# MCU_BLE_Module.net
KiCad netlist of a schematic drawn in Altium Designer
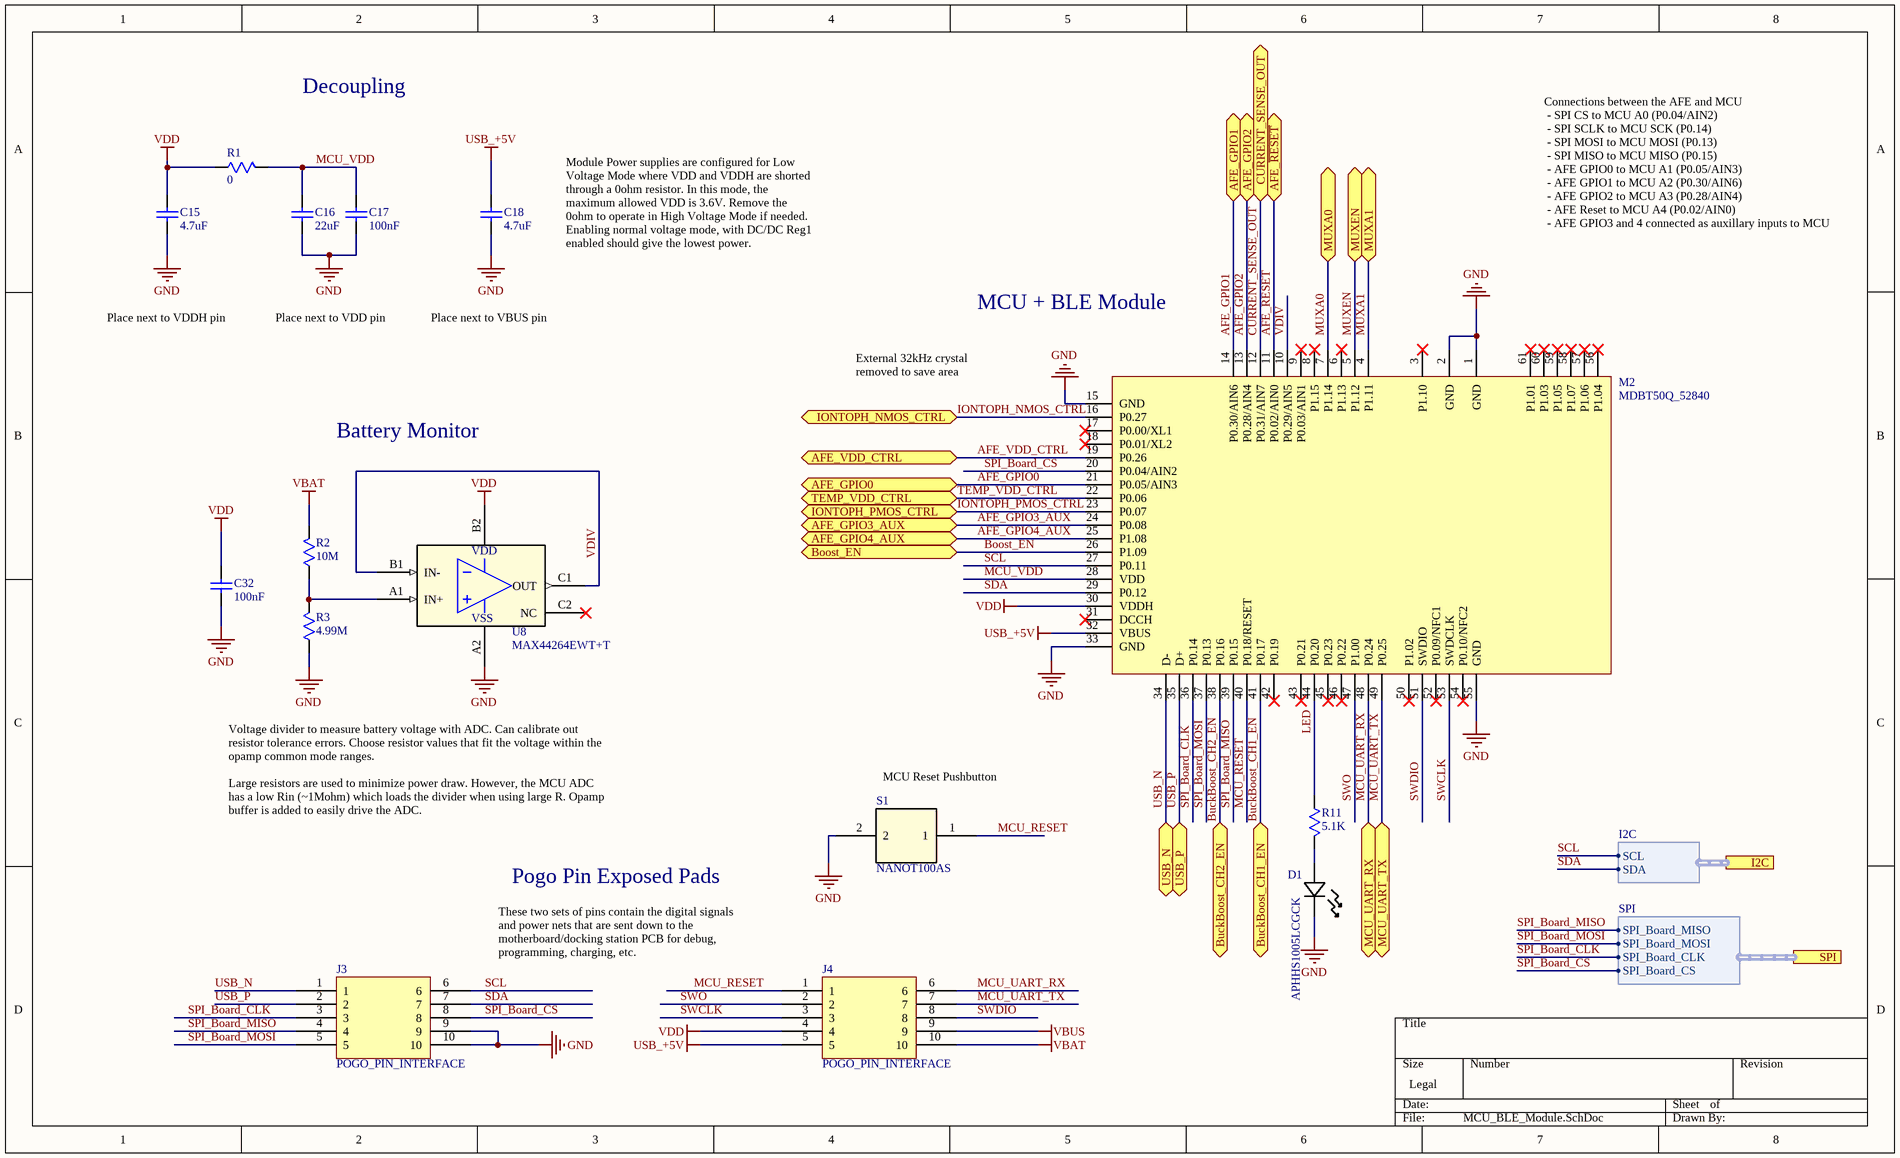
[diagram p0: MCU_BLE_Module.SchDoc]

(export (version "E")
  (design (tool "Eeschema 10.0.6"))
  (components
    (comp (ref "C15")
      (value "4.7uF")
      (footprint "0201 cap")
      (description "Multilayer Chip Capacitor")
      (fields (field (name "Comment") "CAP") (field (name "DESIGNER") "OMIGA"))
      (libsource (lib "Schlib") (part "CAP SMD"))
    )
    (comp (ref "C16")
      (value "22uF")
      (footprint "0402-CAP")
      (description "Multilayer Chip Capacitor")
      (fields (field (name "Comment") "CAP") (field (name "DESIGNER") "OMIGA"))
      (libsource (lib "Schlib") (part "CAP SMD"))
    )
    (comp (ref "C17")
      (value "100nF")
      (footprint "0201 cap")
      (description "Multilayer Chip Capacitor")
      (fields (field (name "Comment") "CAP") (field (name "DESIGNER") "OMIGA"))
      (libsource (lib "Schlib") (part "CAP SMD"))
    )
    (comp (ref "C18")
      (value "4.7uF")
      (footprint "0201 cap")
      (description "Multilayer Chip Capacitor")
      (fields (field (name "Comment") "CAP") (field (name "DESIGNER") "OMIGA"))
      (libsource (lib "Schlib") (part "CAP SMD"))
    )
    (comp (ref "C32")
      (value "100nF")
      (footprint "0201 cap")
      (description "Multilayer Chip Capacitor")
      (fields (field (name "Comment") "CAP") (field (name "DESIGNER") "OMIGA"))
      (libsource (lib "Schlib") (part "CAP SMD"))
    )
    (comp (ref "D1")
      (value "APHHS1005LCGCK")
      (footprint "0402-LED")
      (description "Green LED 0402")
      (fields (field (name "COPYRIGHT") "Copyright (C) 2022 Ultra Librarian. All rights reserved."))
      (libsource (lib "Schlib") (part "APHHS1005LCGCK"))
    )
    (comp (ref "J3")
      (value "POGO_PIN_INTERFACE")
      (footprint "POGO_PIN_INTERFACE_10pin")
      (libsource (lib "Schlib") (part "POGO_PIN_INTERFACE"))
    )
    (comp (ref "J4")
      (value "POGO_PIN_INTERFACE")
      (footprint "POGO_PIN_INTERFACE_10pin")
      (libsource (lib "Schlib") (part "POGO_PIN_INTERFACE"))
    )
    (comp (ref "M2")
      (value "MDBT50Q_52840")
      (footprint "MDBT50Q")
      (libsource (lib "Modules") (part "MDBT50Q_52840"))
    )
    (comp (ref "R1")
      (value "0")
      (footprint "0201 res")
      (description "Surface Mount Resistor")
      (fields (field (name "Comment") "RES") (field (name "DESIGNER") "OMIGA"))
      (libsource (lib "Schlib") (part "RES SMD"))
    )
    (comp (ref "R2")
      (value "10M")
      (footprint "0402-RES")
      (description "Surface Mount Resistor")
      (fields (field (name "Comment") "RES") (field (name "DESIGNER") "OMIGA"))
      (libsource (lib "Schlib") (part "RES SMD"))
    )
    (comp (ref "R3")
      (value "4.99M")
      (footprint "0402-RES")
      (description "Surface Mount Resistor")
      (fields (field (name "Comment") "RES") (field (name "DESIGNER") "OMIGA"))
      (libsource (lib "Schlib") (part "RES SMD"))
    )
    (comp (ref "R11")
      (value "5.1K")
      (footprint "0201 res")
      (description "Surface Mount Resistor")
      (fields (field (name "Comment") "RES") (field (name "DESIGNER") "OMIGA"))
      (libsource (lib "Schlib") (part "RES SMD"))
    )
    (comp (ref "S1")
      (value "NANOT100AS")
      (footprint "NANOT100AS_CNK-M")
      (description "Smallest Push Button Switch")
      (fields (field (name "COPYRIGHT") "Copyright (C) 2022 Ultra Librarian. All rights reserved."))
      (libsource (lib "Schlib") (part "NANOT100AS"))
    )
    (comp (ref "U8")
      (value "MAX44264EWT+T")
      (footprint "21-0217D_W61B1-1_MXM")
      (description "No Description Available")
      (fields (field (name "COPYRIGHT") "Copyright (C) 2022 Ultra Librarian. All rights reserved."))
      (libsource (lib "Schlib") (part "MAX44264EWT+T"))
    )
  )
  (nets
    (net (code "3") (name "/AFE_GPIO0") (class "Default")
      (node (ref "M2") (pin "21") (pinfunction "P0.05/AIN3_21") (pintype "passive"))
    )
    (net (code "4") (name "/AFE_GPIO1") (class "Default")
      (node (ref "M2") (pin "14") (pinfunction "P0.30/AIN6_14") (pintype "passive"))
    )
    (net (code "5") (name "/AFE_GPIO2") (class "Default")
      (node (ref "M2") (pin "13") (pinfunction "P0.28/AIN4_13") (pintype "passive"))
    )
    (net (code "6") (name "/AFE_GPIO3_AUX") (class "Default")
      (node (ref "M2") (pin "24") (pinfunction "P0.08_24") (pintype "passive"))
    )
    (net (code "7") (name "/AFE_GPIO4_AUX") (class "Default")
      (node (ref "M2") (pin "25") (pinfunction "P1.08_25") (pintype "passive"))
    )
    (net (code "8") (name "/AFE_VDD_CTRL") (class "Default")
      (node (ref "M2") (pin "19") (pinfunction "P0.26_19") (pintype "passive"))
    )
    (net (code "9") (name "/AFE_~{RESET}") (class "Default")
      (node (ref "M2") (pin "11") (pinfunction "P0.02/AIN0_11") (pintype "passive"))
    )
    (net (code "10") (name "/Boost_EN") (class "Default")
      (node (ref "M2") (pin "26") (pinfunction "P1.09_26") (pintype "passive"))
    )
    (net (code "11") (name "/BuckBoost_CH1_EN") (class "Default")
      (node (ref "M2") (pin "41") (pinfunction "P0.17_41") (pintype "passive"))
    )
    (net (code "12") (name "/BuckBoost_CH2_EN") (class "Default")
      (node (ref "M2") (pin "38") (pinfunction "P0.16_38") (pintype "passive"))
    )
    (net (code "13") (name "/CURRENT_SENSE_OUT") (class "Default")
      (node (ref "M2") (pin "12") (pinfunction "P0.31/AIN7_12") (pintype "passive"))
    )
    (net (code "14") (name "/IONTOPH_NMOS_CTRL") (class "Default")
      (node (ref "M2") (pin "16") (pinfunction "P0.27_16") (pintype "passive"))
    )
    (net (code "15") (name "/IONTOPH_PMOS_CTRL") (class "Default")
      (node (ref "M2") (pin "23") (pinfunction "P0.07_23") (pintype "passive"))
    )
    (net (code "16") (name "/LED") (class "Default")
      (node (ref "M2") (pin "44") (pinfunction "P0.20_44") (pintype "passive"))
      (node (ref "R11") (pin "1") (pinfunction "1_1") (pintype "passive"))
    )
    (net (code "17") (name "/MCU_RESET") (class "Default")
      (node (ref "J4") (pin "1") (pinfunction "1_1") (pintype "passive"))
      (node (ref "M2") (pin "40") (pinfunction "P0.18/RESET_40") (pintype "passive"))
      (node (ref "S1") (pin "1") (pinfunction "1_1") (pintype "passive"))
    )
    (net (code "18") (name "/MCU_UART_RX") (class "Default")
      (node (ref "J4") (pin "6") (pinfunction "6_6") (pintype "passive"))
      (node (ref "M2") (pin "48") (pinfunction "P0.24_48") (pintype "passive"))
    )
    (net (code "19") (name "/MCU_UART_TX") (class "Default")
      (node (ref "J4") (pin "7") (pinfunction "7_7") (pintype "passive"))
      (node (ref "M2") (pin "49") (pinfunction "P0.25_49") (pintype "passive"))
    )
    (net (code "20") (name "/MCU_VDD") (class "Default")
      (node (ref "C16") (pin "1") (pinfunction "1_1") (pintype "passive"))
      (node (ref "C17") (pin "1") (pinfunction "1_1") (pintype "passive"))
      (node (ref "M2") (pin "28") (pinfunction "VDD_28") (pintype "passive"))
      (node (ref "R1") (pin "2") (pinfunction "2_2") (pintype "passive"))
    )
    (net (code "21") (name "/MUXA0") (class "Default")
      (node (ref "M2") (pin "7") (pinfunction "P1.14_7") (pintype "passive"))
    )
    (net (code "22") (name "/MUXA1") (class "Default")
      (node (ref "M2") (pin "4") (pinfunction "P1.11_4") (pintype "passive"))
    )
    (net (code "23") (name "/MUXEN") (class "Default")
      (node (ref "M2") (pin "5") (pinfunction "P1.12_5") (pintype "passive"))
    )
    (net (code "24") (name "/SCL") (class "Default")
      (node (ref "J3") (pin "6") (pinfunction "6_6") (pintype "passive"))
      (node (ref "M2") (pin "27") (pinfunction "P0.11_27") (pintype "passive"))
    )
    (net (code "25") (name "/SDA") (class "Default")
      (node (ref "J3") (pin "7") (pinfunction "7_7") (pintype "passive"))
      (node (ref "M2") (pin "29") (pinfunction "P0.12_29") (pintype "passive"))
    )
    (net (code "26") (name "/SPI_Board_CLK") (class "Default")
      (node (ref "J3") (pin "3") (pinfunction "3_3") (pintype "passive"))
      (node (ref "M2") (pin "36") (pinfunction "P0.14_36") (pintype "passive"))
    )
    (net (code "27") (name "/SPI_Board_CS") (class "Default")
      (node (ref "J3") (pin "8") (pinfunction "8_8") (pintype "passive"))
      (node (ref "M2") (pin "20") (pinfunction "P0.04/AIN2_20") (pintype "passive"))
    )
    (net (code "28") (name "/SPI_Board_MISO") (class "Default")
      (node (ref "J3") (pin "4") (pinfunction "4_4") (pintype "passive"))
      (node (ref "M2") (pin "39") (pinfunction "P0.15_39") (pintype "passive"))
    )
    (net (code "29") (name "/SPI_Board_MOSI") (class "Default")
      (node (ref "J3") (pin "5") (pinfunction "5_5") (pintype "passive"))
      (node (ref "M2") (pin "37") (pinfunction "P0.13_37") (pintype "passive"))
    )
    (net (code "30") (name "/SWCLK") (class "Default")
      (node (ref "J4") (pin "3") (pinfunction "3_3") (pintype "passive"))
      (node (ref "M2") (pin "53") (pinfunction "SWDCLK_53") (pintype "passive"))
    )
    (net (code "31") (name "/SWDIO") (class "Default")
      (node (ref "J4") (pin "8") (pinfunction "8_8") (pintype "passive"))
      (node (ref "M2") (pin "51") (pinfunction "SWDIO_51") (pintype "passive"))
    )
    (net (code "32") (name "/SWO") (class "Default")
      (node (ref "J4") (pin "2") (pinfunction "2_2") (pintype "passive"))
      (node (ref "M2") (pin "47") (pinfunction "P1.00_47") (pintype "passive"))
    )
    (net (code "33") (name "/TEMP_VDD_CTRL") (class "Default")
      (node (ref "M2") (pin "22") (pinfunction "P0.06_22") (pintype "passive"))
    )
    (net (code "34") (name "/USB_N") (class "Default")
      (node (ref "J3") (pin "1") (pinfunction "1_1") (pintype "passive"))
      (node (ref "M2") (pin "34") (pinfunction "D-_34") (pintype "passive"))
    )
    (net (code "35") (name "/USB_P") (class "Default")
      (node (ref "J3") (pin "2") (pinfunction "2_2") (pintype "passive"))
      (node (ref "M2") (pin "35") (pinfunction "D+_35") (pintype "passive"))
    )
    (net (code "36") (name "/VDIV") (class "Default")
      (node (ref "M2") (pin "10") (pinfunction "P0.29/AIN5_10") (pintype "passive"))
      (node (ref "U8") (pin "B1") (pinfunction "IN-_B1") (pintype "input"))
      (node (ref "U8") (pin "C1") (pinfunction "OUT_C1") (pintype "output"))
    )
    (net (code "39") (name "GND") (class "Default")
      (node (ref "C15") (pin "2") (pinfunction "2_2") (pintype "passive"))
      (node (ref "C16") (pin "2") (pinfunction "2_2") (pintype "passive"))
      (node (ref "C17") (pin "2") (pinfunction "2_2") (pintype "passive"))
      (node (ref "C18") (pin "2") (pinfunction "2_2") (pintype "passive"))
      (node (ref "C32") (pin "2") (pinfunction "2_2") (pintype "passive"))
      (node (ref "D1") (pin "1") (pinfunction "1_1") (pintype "passive"))
      (node (ref "J3") (pin "10") (pinfunction "10_10") (pintype "passive"))
      (node (ref "J3") (pin "9") (pinfunction "9_9") (pintype "passive"))
      (node (ref "M2") (pin "1") (pinfunction "GND_1") (pintype "passive"))
      (node (ref "M2") (pin "15") (pinfunction "GND_15") (pintype "passive"))
      (node (ref "M2") (pin "2") (pinfunction "GND_2") (pintype "passive"))
      (node (ref "M2") (pin "33") (pinfunction "GND_33") (pintype "passive"))
      (node (ref "M2") (pin "55") (pinfunction "GND_55") (pintype "passive"))
      (node (ref "R3") (pin "1") (pinfunction "1_1") (pintype "passive"))
      (node (ref "S1") (pin "2") (pinfunction "2_2") (pintype "passive"))
      (node (ref "U8") (pin "A2") (pinfunction "VSS_A2") (pintype "power_in"))
    )
    (net (code "40") (name "Net-(D1-Pad2)") (class "Default")
      (node (ref "D1") (pin "2") (pinfunction "2_2") (pintype "passive"))
      (node (ref "R11") (pin "2") (pinfunction "2_2") (pintype "passive"))
    )
    (net (code "41") (name "Net-(U8-IN+)") (class "Default")
      (node (ref "R2") (pin "1") (pinfunction "1_1") (pintype "passive"))
      (node (ref "R3") (pin "2") (pinfunction "2_2") (pintype "passive"))
      (node (ref "U8") (pin "A1") (pinfunction "IN+_A1") (pintype "input"))
    )
    (net (code "42") (name "USB_+5V") (class "Default")
      (node (ref "C18") (pin "1") (pinfunction "1_1") (pintype "passive"))
      (node (ref "J4") (pin "5") (pinfunction "5_5") (pintype "passive"))
      (node (ref "M2") (pin "32") (pinfunction "VBUS_32") (pintype "passive"))
    )
    (net (code "43") (name "VBAT") (class "Default")
      (node (ref "J4") (pin "10") (pinfunction "10_10") (pintype "passive"))
      (node (ref "R2") (pin "2") (pinfunction "2_2") (pintype "passive"))
    )
    (net (code "44") (name "VBUS") (class "Default")
      (node (ref "J4") (pin "9") (pinfunction "9_9") (pintype "passive"))
    )
    (net (code "45") (name "VDD") (class "Default")
      (node (ref "C15") (pin "1") (pinfunction "1_1") (pintype "passive"))
      (node (ref "C32") (pin "1") (pinfunction "1_1") (pintype "passive"))
      (node (ref "J4") (pin "4") (pinfunction "4_4") (pintype "passive"))
      (node (ref "M2") (pin "30") (pinfunction "VDDH_30") (pintype "passive"))
      (node (ref "R1") (pin "1") (pinfunction "1_1") (pintype "passive"))
      (node (ref "U8") (pin "B2") (pinfunction "VDD_B2") (pintype "power_in"))
    )
    (net (code "46") (name "unconnected-(M2-DCCH-Pad31)") (class "Default")
      (node (ref "M2") (pin "31") (pinfunction "DCCH_31") (pintype "passive+no_connect"))
    )
    (net (code "47") (name "unconnected-(M2-P0.00{slash}XL1-Pad17)") (class "Default")
      (node (ref "M2") (pin "17") (pinfunction "P0.00/XL1_17") (pintype "passive+no_connect"))
    )
    (net (code "48") (name "unconnected-(M2-P0.01{slash}XL2-Pad18)") (class "Default")
      (node (ref "M2") (pin "18") (pinfunction "P0.01/XL2_18") (pintype "passive+no_connect"))
    )
    (net (code "49") (name "unconnected-(M2-P0.03{slash}AIN1-Pad9)") (class "Default")
      (node (ref "M2") (pin "9") (pinfunction "P0.03/AIN1_9") (pintype "passive+no_connect"))
    )
    (net (code "50") (name "unconnected-(M2-P0.09{slash}NFC1-Pad52)") (class "Default")
      (node (ref "M2") (pin "52") (pinfunction "P0.09/NFC1_52") (pintype "passive+no_connect"))
    )
    (net (code "51") (name "unconnected-(M2-P0.10{slash}NFC2-Pad54)") (class "Default")
      (node (ref "M2") (pin "54") (pinfunction "P0.10/NFC2_54") (pintype "passive+no_connect"))
    )
    (net (code "52") (name "unconnected-(M2-P0.19-Pad42)") (class "Default")
      (node (ref "M2") (pin "42") (pinfunction "P0.19_42") (pintype "passive+no_connect"))
    )
    (net (code "53") (name "unconnected-(M2-P0.21-Pad43)") (class "Default")
      (node (ref "M2") (pin "43") (pinfunction "P0.21_43") (pintype "passive+no_connect"))
    )
    (net (code "54") (name "unconnected-(M2-P0.22-Pad46)") (class "Default")
      (node (ref "M2") (pin "46") (pinfunction "P0.22_46") (pintype "passive+no_connect"))
    )
    (net (code "55") (name "unconnected-(M2-P0.23-Pad45)") (class "Default")
      (node (ref "M2") (pin "45") (pinfunction "P0.23_45") (pintype "passive+no_connect"))
    )
    (net (code "56") (name "unconnected-(M2-P1.01-Pad61)") (class "Default")
      (node (ref "M2") (pin "61") (pinfunction "P1.01_61") (pintype "passive+no_connect"))
    )
    (net (code "57") (name "unconnected-(M2-P1.02-Pad50)") (class "Default")
      (node (ref "M2") (pin "50") (pinfunction "P1.02_50") (pintype "passive+no_connect"))
    )
    (net (code "58") (name "unconnected-(M2-P1.03-Pad60)") (class "Default")
      (node (ref "M2") (pin "60") (pinfunction "P1.03_60") (pintype "passive+no_connect"))
    )
    (net (code "59") (name "unconnected-(M2-P1.04-Pad56)") (class "Default")
      (node (ref "M2") (pin "56") (pinfunction "P1.04_56") (pintype "passive+no_connect"))
    )
    (net (code "60") (name "unconnected-(M2-P1.05-Pad59)") (class "Default")
      (node (ref "M2") (pin "59") (pinfunction "P1.05_59") (pintype "passive+no_connect"))
    )
    (net (code "61") (name "unconnected-(M2-P1.06-Pad57)") (class "Default")
      (node (ref "M2") (pin "57") (pinfunction "P1.06_57") (pintype "passive+no_connect"))
    )
    (net (code "62") (name "unconnected-(M2-P1.07-Pad58)") (class "Default")
      (node (ref "M2") (pin "58") (pinfunction "P1.07_58") (pintype "passive+no_connect"))
    )
    (net (code "63") (name "unconnected-(M2-P1.10-Pad3)") (class "Default")
      (node (ref "M2") (pin "3") (pinfunction "P1.10_3") (pintype "passive+no_connect"))
    )
    (net (code "64") (name "unconnected-(M2-P1.13-Pad6)") (class "Default")
      (node (ref "M2") (pin "6") (pinfunction "P1.13_6") (pintype "passive+no_connect"))
    )
    (net (code "65") (name "unconnected-(M2-P1.15-Pad8)") (class "Default")
      (node (ref "M2") (pin "8") (pinfunction "P1.15_8") (pintype "passive+no_connect"))
    )
    (net (code "66") (name "unconnected-(U8-NC-PadC2)") (class "Default")
      (node (ref "U8") (pin "C2") (pinfunction "NC_C2") (pintype "passive+no_connect"))
    )
  )
)
